# Relay_Sheet.net
KiCad netlist of a schematic drawn in Altium Designer
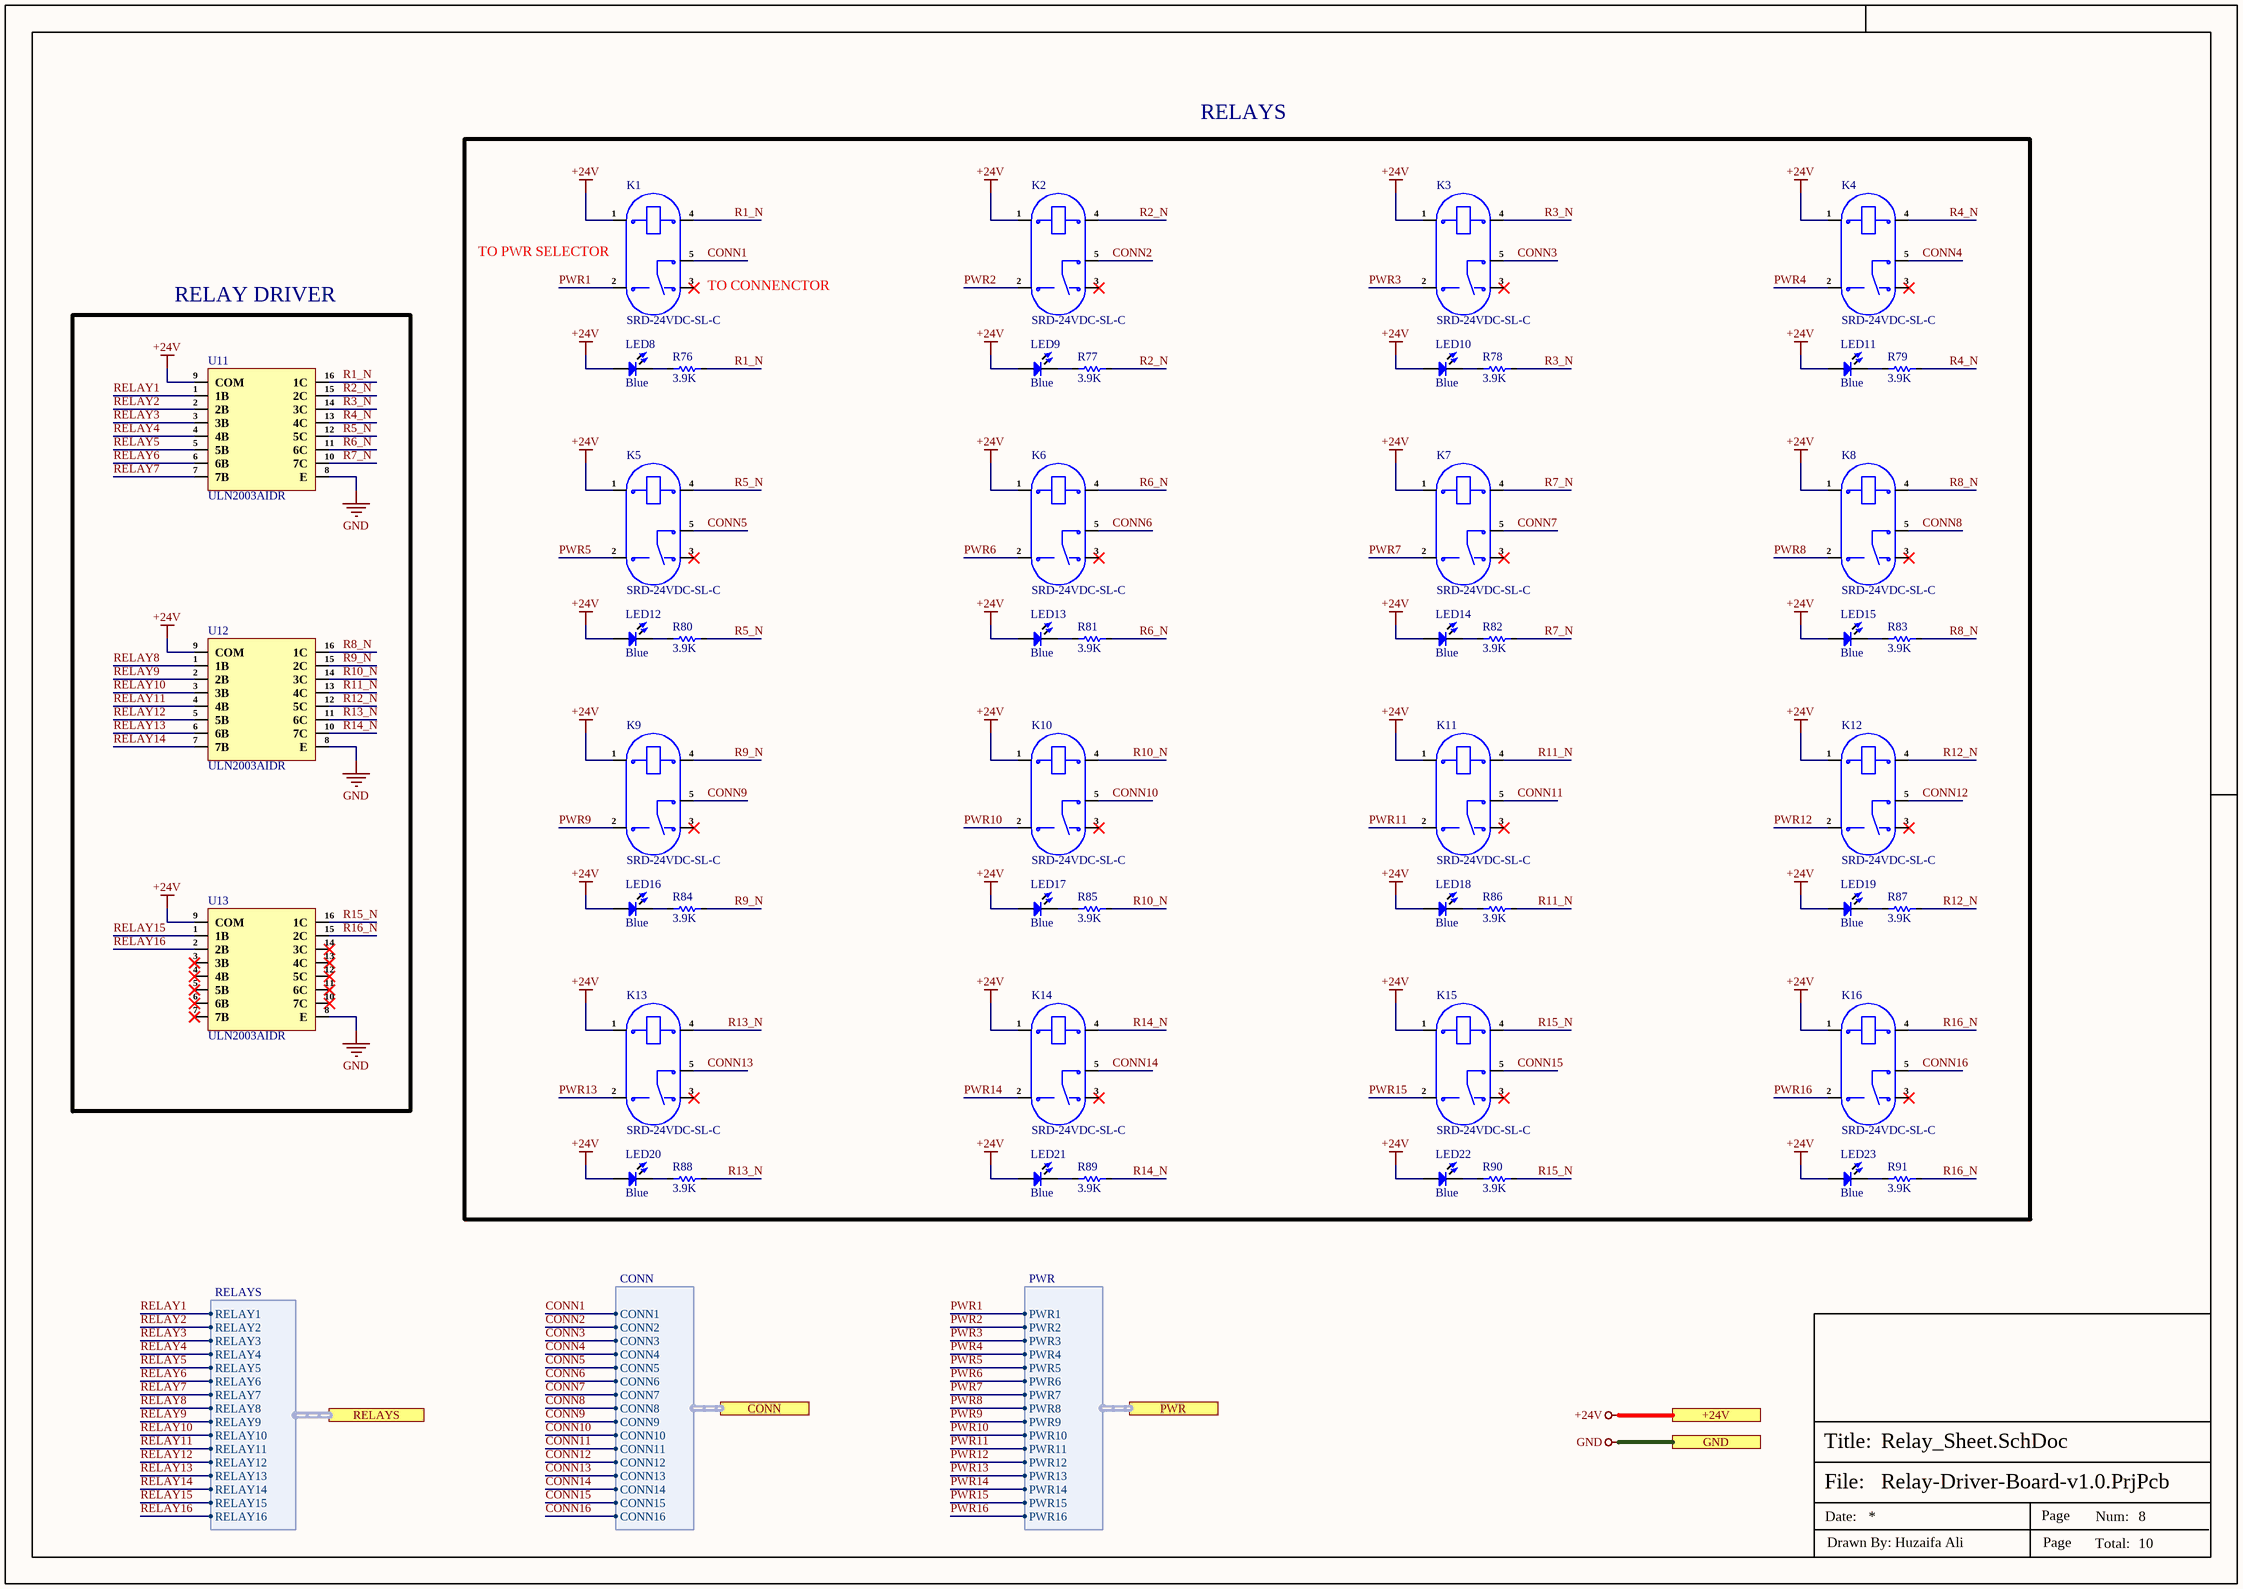
[diagram p0: Relay_Sheet.SchDoc]

(export (version "E")
  (design (tool "Eeschema 10.0.6"))
  (components
    (comp (ref "K1")
      (value "SRD-24VDC-SL-C")
      (footprint "SRD-24VDC-SL-C")
      (description "250V@AC 24V 15A SPDT (1 Form C) Plugin,15.6x19.2mm Power Relays ROHS")
      (fields (field (name "LCSC PART NUMBER") "C15840") (field (name "MANUFACTURER") "Ningbo Forward Relay"))
      (libsource (lib "eSpark Libraries") (part "SRD-24VDC-SL-C"))
    )
    (comp (ref "K2")
      (value "SRD-24VDC-SL-C")
      (footprint "SRD-24VDC-SL-C")
      (description "250V@AC 24V 15A SPDT (1 Form C) Plugin,15.6x19.2mm Power Relays ROHS")
      (fields (field (name "LCSC PART NUMBER") "C15840") (field (name "MANUFACTURER") "Ningbo Forward Relay"))
      (libsource (lib "eSpark Libraries") (part "SRD-24VDC-SL-C"))
    )
    (comp (ref "K3")
      (value "SRD-24VDC-SL-C")
      (footprint "SRD-24VDC-SL-C")
      (description "250V@AC 24V 15A SPDT (1 Form C) Plugin,15.6x19.2mm Power Relays ROHS")
      (fields (field (name "LCSC PART NUMBER") "C15840") (field (name "MANUFACTURER") "Ningbo Forward Relay"))
      (libsource (lib "eSpark Libraries") (part "SRD-24VDC-SL-C"))
    )
    (comp (ref "K4")
      (value "SRD-24VDC-SL-C")
      (footprint "SRD-24VDC-SL-C")
      (description "250V@AC 24V 15A SPDT (1 Form C) Plugin,15.6x19.2mm Power Relays ROHS")
      (fields (field (name "LCSC PART NUMBER") "C15840") (field (name "MANUFACTURER") "Ningbo Forward Relay"))
      (libsource (lib "eSpark Libraries") (part "SRD-24VDC-SL-C"))
    )
    (comp (ref "K5")
      (value "SRD-24VDC-SL-C")
      (footprint "SRD-24VDC-SL-C")
      (description "250V@AC 24V 15A SPDT (1 Form C) Plugin,15.6x19.2mm Power Relays ROHS")
      (fields (field (name "LCSC PART NUMBER") "C15840") (field (name "MANUFACTURER") "Ningbo Forward Relay"))
      (libsource (lib "eSpark Libraries") (part "SRD-24VDC-SL-C"))
    )
    (comp (ref "K6")
      (value "SRD-24VDC-SL-C")
      (footprint "SRD-24VDC-SL-C")
      (description "250V@AC 24V 15A SPDT (1 Form C) Plugin,15.6x19.2mm Power Relays ROHS")
      (fields (field (name "LCSC PART NUMBER") "C15840") (field (name "MANUFACTURER") "Ningbo Forward Relay"))
      (libsource (lib "eSpark Libraries") (part "SRD-24VDC-SL-C"))
    )
    (comp (ref "K7")
      (value "SRD-24VDC-SL-C")
      (footprint "SRD-24VDC-SL-C")
      (description "250V@AC 24V 15A SPDT (1 Form C) Plugin,15.6x19.2mm Power Relays ROHS")
      (fields (field (name "LCSC PART NUMBER") "C15840") (field (name "MANUFACTURER") "Ningbo Forward Relay"))
      (libsource (lib "eSpark Libraries") (part "SRD-24VDC-SL-C"))
    )
    (comp (ref "K8")
      (value "SRD-24VDC-SL-C")
      (footprint "SRD-24VDC-SL-C")
      (description "250V@AC 24V 15A SPDT (1 Form C) Plugin,15.6x19.2mm Power Relays ROHS")
      (fields (field (name "LCSC PART NUMBER") "C15840") (field (name "MANUFACTURER") "Ningbo Forward Relay"))
      (libsource (lib "eSpark Libraries") (part "SRD-24VDC-SL-C"))
    )
    (comp (ref "K9")
      (value "SRD-24VDC-SL-C")
      (footprint "SRD-24VDC-SL-C")
      (description "250V@AC 24V 15A SPDT (1 Form C) Plugin,15.6x19.2mm Power Relays ROHS")
      (fields (field (name "LCSC PART NUMBER") "C15840") (field (name "MANUFACTURER") "Ningbo Forward Relay"))
      (libsource (lib "eSpark Libraries") (part "SRD-24VDC-SL-C"))
    )
    (comp (ref "K10")
      (value "SRD-24VDC-SL-C")
      (footprint "SRD-24VDC-SL-C")
      (description "250V@AC 24V 15A SPDT (1 Form C) Plugin,15.6x19.2mm Power Relays ROHS")
      (fields (field (name "LCSC PART NUMBER") "C15840") (field (name "MANUFACTURER") "Ningbo Forward Relay"))
      (libsource (lib "eSpark Libraries") (part "SRD-24VDC-SL-C"))
    )
    (comp (ref "K11")
      (value "SRD-24VDC-SL-C")
      (footprint "SRD-24VDC-SL-C")
      (description "250V@AC 24V 15A SPDT (1 Form C) Plugin,15.6x19.2mm Power Relays ROHS")
      (fields (field (name "LCSC PART NUMBER") "C15840") (field (name "MANUFACTURER") "Ningbo Forward Relay"))
      (libsource (lib "eSpark Libraries") (part "SRD-24VDC-SL-C"))
    )
    (comp (ref "K12")
      (value "SRD-24VDC-SL-C")
      (footprint "SRD-24VDC-SL-C")
      (description "250V@AC 24V 15A SPDT (1 Form C) Plugin,15.6x19.2mm Power Relays ROHS")
      (fields (field (name "LCSC PART NUMBER") "C15840") (field (name "MANUFACTURER") "Ningbo Forward Relay"))
      (libsource (lib "eSpark Libraries") (part "SRD-24VDC-SL-C"))
    )
    (comp (ref "K13")
      (value "SRD-24VDC-SL-C")
      (footprint "SRD-24VDC-SL-C")
      (description "250V@AC 24V 15A SPDT (1 Form C) Plugin,15.6x19.2mm Power Relays ROHS")
      (fields (field (name "LCSC PART NUMBER") "C15840") (field (name "MANUFACTURER") "Ningbo Forward Relay"))
      (libsource (lib "eSpark Libraries") (part "SRD-24VDC-SL-C"))
    )
    (comp (ref "K14")
      (value "SRD-24VDC-SL-C")
      (footprint "SRD-24VDC-SL-C")
      (description "250V@AC 24V 15A SPDT (1 Form C) Plugin,15.6x19.2mm Power Relays ROHS")
      (fields (field (name "LCSC PART NUMBER") "C15840") (field (name "MANUFACTURER") "Ningbo Forward Relay"))
      (libsource (lib "eSpark Libraries") (part "SRD-24VDC-SL-C"))
    )
    (comp (ref "K15")
      (value "SRD-24VDC-SL-C")
      (footprint "SRD-24VDC-SL-C")
      (description "250V@AC 24V 15A SPDT (1 Form C) Plugin,15.6x19.2mm Power Relays ROHS")
      (fields (field (name "LCSC PART NUMBER") "C15840") (field (name "MANUFACTURER") "Ningbo Forward Relay"))
      (libsource (lib "eSpark Libraries") (part "SRD-24VDC-SL-C"))
    )
    (comp (ref "K16")
      (value "SRD-24VDC-SL-C")
      (footprint "SRD-24VDC-SL-C")
      (description "250V@AC 24V 15A SPDT (1 Form C) Plugin,15.6x19.2mm Power Relays ROHS")
      (fields (field (name "LCSC PART NUMBER") "C15840") (field (name "MANUFACTURER") "Ningbo Forward Relay"))
      (libsource (lib "eSpark Libraries") (part "SRD-24VDC-SL-C"))
    )
    (comp (ref "LED8")
      (value "Blue")
      (footprint "LED-0603")
      (description "blue 0603 Light Emitting Diodes (LED) ROHS")
      (fields
        (field (name "MANUFACTURER") "Foshan NationStar Optoelectronics")
        (field (name "MANUFACTURER PART NUMBER") "NCD0603B3")
      )
      (libsource (lib "eSpark Libraries") (part "NCD0603B3"))
    )
    (comp (ref "LED9")
      (value "Blue")
      (footprint "LED-0603")
      (description "blue 0603 Light Emitting Diodes (LED) ROHS")
      (fields
        (field (name "MANUFACTURER") "Foshan NationStar Optoelectronics")
        (field (name "MANUFACTURER PART NUMBER") "NCD0603B3")
      )
      (libsource (lib "eSpark Libraries") (part "NCD0603B3"))
    )
    (comp (ref "LED10")
      (value "Blue")
      (footprint "LED-0603")
      (description "blue 0603 Light Emitting Diodes (LED) ROHS")
      (fields
        (field (name "MANUFACTURER") "Foshan NationStar Optoelectronics")
        (field (name "MANUFACTURER PART NUMBER") "NCD0603B3")
      )
      (libsource (lib "eSpark Libraries") (part "NCD0603B3"))
    )
    (comp (ref "LED11")
      (value "Blue")
      (footprint "LED-0603")
      (description "blue 0603 Light Emitting Diodes (LED) ROHS")
      (fields
        (field (name "MANUFACTURER") "Foshan NationStar Optoelectronics")
        (field (name "MANUFACTURER PART NUMBER") "NCD0603B3")
      )
      (libsource (lib "eSpark Libraries") (part "NCD0603B3"))
    )
    (comp (ref "LED12")
      (value "Blue")
      (footprint "LED-0603")
      (description "blue 0603 Light Emitting Diodes (LED) ROHS")
      (fields
        (field (name "MANUFACTURER") "Foshan NationStar Optoelectronics")
        (field (name "MANUFACTURER PART NUMBER") "NCD0603B3")
      )
      (libsource (lib "eSpark Libraries") (part "NCD0603B3"))
    )
    (comp (ref "LED13")
      (value "Blue")
      (footprint "LED-0603")
      (description "blue 0603 Light Emitting Diodes (LED) ROHS")
      (fields
        (field (name "MANUFACTURER") "Foshan NationStar Optoelectronics")
        (field (name "MANUFACTURER PART NUMBER") "NCD0603B3")
      )
      (libsource (lib "eSpark Libraries") (part "NCD0603B3"))
    )
    (comp (ref "LED14")
      (value "Blue")
      (footprint "LED-0603")
      (description "blue 0603 Light Emitting Diodes (LED) ROHS")
      (fields
        (field (name "MANUFACTURER") "Foshan NationStar Optoelectronics")
        (field (name "MANUFACTURER PART NUMBER") "NCD0603B3")
      )
      (libsource (lib "eSpark Libraries") (part "NCD0603B3"))
    )
    (comp (ref "LED15")
      (value "Blue")
      (footprint "LED-0603")
      (description "blue 0603 Light Emitting Diodes (LED) ROHS")
      (fields
        (field (name "MANUFACTURER") "Foshan NationStar Optoelectronics")
        (field (name "MANUFACTURER PART NUMBER") "NCD0603B3")
      )
      (libsource (lib "eSpark Libraries") (part "NCD0603B3"))
    )
    (comp (ref "LED16")
      (value "Blue")
      (footprint "LED-0603")
      (description "blue 0603 Light Emitting Diodes (LED) ROHS")
      (fields
        (field (name "MANUFACTURER") "Foshan NationStar Optoelectronics")
        (field (name "MANUFACTURER PART NUMBER") "NCD0603B3")
      )
      (libsource (lib "eSpark Libraries") (part "NCD0603B3"))
    )
    (comp (ref "LED17")
      (value "Blue")
      (footprint "LED-0603")
      (description "blue 0603 Light Emitting Diodes (LED) ROHS")
      (fields
        (field (name "MANUFACTURER") "Foshan NationStar Optoelectronics")
        (field (name "MANUFACTURER PART NUMBER") "NCD0603B3")
      )
      (libsource (lib "eSpark Libraries") (part "NCD0603B3"))
    )
    (comp (ref "LED18")
      (value "Blue")
      (footprint "LED-0603")
      (description "blue 0603 Light Emitting Diodes (LED) ROHS")
      (fields
        (field (name "MANUFACTURER") "Foshan NationStar Optoelectronics")
        (field (name "MANUFACTURER PART NUMBER") "NCD0603B3")
      )
      (libsource (lib "eSpark Libraries") (part "NCD0603B3"))
    )
    (comp (ref "LED19")
      (value "Blue")
      (footprint "LED-0603")
      (description "blue 0603 Light Emitting Diodes (LED) ROHS")
      (fields
        (field (name "MANUFACTURER") "Foshan NationStar Optoelectronics")
        (field (name "MANUFACTURER PART NUMBER") "NCD0603B3")
      )
      (libsource (lib "eSpark Libraries") (part "NCD0603B3"))
    )
    (comp (ref "LED20")
      (value "Blue")
      (footprint "LED-0603")
      (description "blue 0603 Light Emitting Diodes (LED) ROHS")
      (fields
        (field (name "MANUFACTURER") "Foshan NationStar Optoelectronics")
        (field (name "MANUFACTURER PART NUMBER") "NCD0603B3")
      )
      (libsource (lib "eSpark Libraries") (part "NCD0603B3"))
    )
    (comp (ref "LED21")
      (value "Blue")
      (footprint "LED-0603")
      (description "blue 0603 Light Emitting Diodes (LED) ROHS")
      (fields
        (field (name "MANUFACTURER") "Foshan NationStar Optoelectronics")
        (field (name "MANUFACTURER PART NUMBER") "NCD0603B3")
      )
      (libsource (lib "eSpark Libraries") (part "NCD0603B3"))
    )
    (comp (ref "LED22")
      (value "Blue")
      (footprint "LED-0603")
      (description "blue 0603 Light Emitting Diodes (LED) ROHS")
      (fields
        (field (name "MANUFACTURER") "Foshan NationStar Optoelectronics")
        (field (name "MANUFACTURER PART NUMBER") "NCD0603B3")
      )
      (libsource (lib "eSpark Libraries") (part "NCD0603B3"))
    )
    (comp (ref "LED23")
      (value "Blue")
      (footprint "LED-0603")
      (description "blue 0603 Light Emitting Diodes (LED) ROHS")
      (fields
        (field (name "MANUFACTURER") "Foshan NationStar Optoelectronics")
        (field (name "MANUFACTURER PART NUMBER") "NCD0603B3")
      )
      (libsource (lib "eSpark Libraries") (part "NCD0603B3"))
    )
    (comp (ref "R76")
      (value "3.9K")
      (footprint "Res-0402")
      (description "RES 3.9K OHM 1% 1/16W 0402")
      (fields
        (field (name "MANUFACTURER") "Yageo")
        (field (name "MANUFACTURER PART NUMBER") "RC0402FR-073K9L")
      )
      (libsource (lib "eSpark Libraries") (part "RC0402FR-073K9L"))
    )
    (comp (ref "R77")
      (value "3.9K")
      (footprint "Res-0402")
      (description "RES 3.9K OHM 1% 1/16W 0402")
      (fields
        (field (name "MANUFACTURER") "Yageo")
        (field (name "MANUFACTURER PART NUMBER") "RC0402FR-073K9L")
      )
      (libsource (lib "eSpark Libraries") (part "RC0402FR-073K9L"))
    )
    (comp (ref "R78")
      (value "3.9K")
      (footprint "Res-0402")
      (description "RES 3.9K OHM 1% 1/16W 0402")
      (fields
        (field (name "MANUFACTURER") "Yageo")
        (field (name "MANUFACTURER PART NUMBER") "RC0402FR-073K9L")
      )
      (libsource (lib "eSpark Libraries") (part "RC0402FR-073K9L"))
    )
    (comp (ref "R79")
      (value "3.9K")
      (footprint "Res-0402")
      (description "RES 3.9K OHM 1% 1/16W 0402")
      (fields
        (field (name "MANUFACTURER") "Yageo")
        (field (name "MANUFACTURER PART NUMBER") "RC0402FR-073K9L")
      )
      (libsource (lib "eSpark Libraries") (part "RC0402FR-073K9L"))
    )
    (comp (ref "R80")
      (value "3.9K")
      (footprint "Res-0402")
      (description "RES 3.9K OHM 1% 1/16W 0402")
      (fields
        (field (name "MANUFACTURER") "Yageo")
        (field (name "MANUFACTURER PART NUMBER") "RC0402FR-073K9L")
      )
      (libsource (lib "eSpark Libraries") (part "RC0402FR-073K9L"))
    )
    (comp (ref "R81")
      (value "3.9K")
      (footprint "Res-0402")
      (description "RES 3.9K OHM 1% 1/16W 0402")
      (fields
        (field (name "MANUFACTURER") "Yageo")
        (field (name "MANUFACTURER PART NUMBER") "RC0402FR-073K9L")
      )
      (libsource (lib "eSpark Libraries") (part "RC0402FR-073K9L"))
    )
    (comp (ref "R82")
      (value "3.9K")
      (footprint "Res-0402")
      (description "RES 3.9K OHM 1% 1/16W 0402")
      (fields
        (field (name "MANUFACTURER") "Yageo")
        (field (name "MANUFACTURER PART NUMBER") "RC0402FR-073K9L")
      )
      (libsource (lib "eSpark Libraries") (part "RC0402FR-073K9L"))
    )
    (comp (ref "R83")
      (value "3.9K")
      (footprint "Res-0402")
      (description "RES 3.9K OHM 1% 1/16W 0402")
      (fields
        (field (name "MANUFACTURER") "Yageo")
        (field (name "MANUFACTURER PART NUMBER") "RC0402FR-073K9L")
      )
      (libsource (lib "eSpark Libraries") (part "RC0402FR-073K9L"))
    )
    (comp (ref "R84")
      (value "3.9K")
      (footprint "Res-0402")
      (description "RES 3.9K OHM 1% 1/16W 0402")
      (fields
        (field (name "MANUFACTURER") "Yageo")
        (field (name "MANUFACTURER PART NUMBER") "RC0402FR-073K9L")
      )
      (libsource (lib "eSpark Libraries") (part "RC0402FR-073K9L"))
    )
    (comp (ref "R85")
      (value "3.9K")
      (footprint "Res-0402")
      (description "RES 3.9K OHM 1% 1/16W 0402")
      (fields
        (field (name "MANUFACTURER") "Yageo")
        (field (name "MANUFACTURER PART NUMBER") "RC0402FR-073K9L")
      )
      (libsource (lib "eSpark Libraries") (part "RC0402FR-073K9L"))
    )
    (comp (ref "R86")
      (value "3.9K")
      (footprint "Res-0402")
      (description "RES 3.9K OHM 1% 1/16W 0402")
      (fields
        (field (name "MANUFACTURER") "Yageo")
        (field (name "MANUFACTURER PART NUMBER") "RC0402FR-073K9L")
      )
      (libsource (lib "eSpark Libraries") (part "RC0402FR-073K9L"))
    )
    (comp (ref "R87")
      (value "3.9K")
      (footprint "Res-0402")
      (description "RES 3.9K OHM 1% 1/16W 0402")
      (fields
        (field (name "MANUFACTURER") "Yageo")
        (field (name "MANUFACTURER PART NUMBER") "RC0402FR-073K9L")
      )
      (libsource (lib "eSpark Libraries") (part "RC0402FR-073K9L"))
    )
    (comp (ref "R88")
      (value "3.9K")
      (footprint "Res-0402")
      (description "RES 3.9K OHM 1% 1/16W 0402")
      (fields
        (field (name "MANUFACTURER") "Yageo")
        (field (name "MANUFACTURER PART NUMBER") "RC0402FR-073K9L")
      )
      (libsource (lib "eSpark Libraries") (part "RC0402FR-073K9L"))
    )
    (comp (ref "R89")
      (value "3.9K")
      (footprint "Res-0402")
      (description "RES 3.9K OHM 1% 1/16W 0402")
      (fields
        (field (name "MANUFACTURER") "Yageo")
        (field (name "MANUFACTURER PART NUMBER") "RC0402FR-073K9L")
      )
      (libsource (lib "eSpark Libraries") (part "RC0402FR-073K9L"))
    )
    (comp (ref "R90")
      (value "3.9K")
      (footprint "Res-0402")
      (description "RES 3.9K OHM 1% 1/16W 0402")
      (fields
        (field (name "MANUFACTURER") "Yageo")
        (field (name "MANUFACTURER PART NUMBER") "RC0402FR-073K9L")
      )
      (libsource (lib "eSpark Libraries") (part "RC0402FR-073K9L"))
    )
    (comp (ref "R91")
      (value "3.9K")
      (footprint "Res-0402")
      (description "RES 3.9K OHM 1% 1/16W 0402")
      (fields
        (field (name "MANUFACTURER") "Yageo")
        (field (name "MANUFACTURER PART NUMBER") "RC0402FR-073K9L")
      )
      (libsource (lib "eSpark Libraries") (part "RC0402FR-073K9L"))
    )
    (comp (ref "U11")
      (value "ULN2003AIDR")
      (footprint "16-SOIC (0.154\", 3.90mm Width)")
      (description "IC PWR RELAY 7NPN 1:1 16SOIC")
      (fields (field (name "MANUFACTURER") "Texas Instruments"))
      (libsource (lib "eSpark Libraries") (part "ULN2003AIDR"))
    )
    (comp (ref "U12")
      (value "ULN2003AIDR")
      (footprint "16-SOIC (0.154\", 3.90mm Width)")
      (description "IC PWR RELAY 7NPN 1:1 16SOIC")
      (fields (field (name "MANUFACTURER") "Texas Instruments"))
      (libsource (lib "eSpark Libraries") (part "ULN2003AIDR"))
    )
    (comp (ref "U13")
      (value "ULN2003AIDR")
      (footprint "16-SOIC (0.154\", 3.90mm Width)")
      (description "IC PWR RELAY 7NPN 1:1 16SOIC")
      (fields (field (name "MANUFACTURER") "Texas Instruments"))
      (libsource (lib "eSpark Libraries") (part "ULN2003AIDR"))
    )
  )
  (nets
    (net (code "4") (name "+24V") (class "Default")
      (node (ref "K1") (pin "1") (pinfunction "1_1") (pintype "passive"))
      (node (ref "K10") (pin "1") (pinfunction "1_1") (pintype "passive"))
      (node (ref "K11") (pin "1") (pinfunction "1_1") (pintype "passive"))
      (node (ref "K12") (pin "1") (pinfunction "1_1") (pintype "passive"))
      (node (ref "K13") (pin "1") (pinfunction "1_1") (pintype "passive"))
      (node (ref "K14") (pin "1") (pinfunction "1_1") (pintype "passive"))
      (node (ref "K15") (pin "1") (pinfunction "1_1") (pintype "passive"))
      (node (ref "K16") (pin "1") (pinfunction "1_1") (pintype "passive"))
      (node (ref "K2") (pin "1") (pinfunction "1_1") (pintype "passive"))
      (node (ref "K3") (pin "1") (pinfunction "1_1") (pintype "passive"))
      (node (ref "K4") (pin "1") (pinfunction "1_1") (pintype "passive"))
      (node (ref "K5") (pin "1") (pinfunction "1_1") (pintype "passive"))
      (node (ref "K6") (pin "1") (pinfunction "1_1") (pintype "passive"))
      (node (ref "K7") (pin "1") (pinfunction "1_1") (pintype "passive"))
      (node (ref "K8") (pin "1") (pinfunction "1_1") (pintype "passive"))
      (node (ref "K9") (pin "1") (pinfunction "1_1") (pintype "passive"))
      (node (ref "LED10") (pin "1") (pinfunction "1_1") (pintype "passive"))
      (node (ref "LED11") (pin "1") (pinfunction "1_1") (pintype "passive"))
      (node (ref "LED12") (pin "1") (pinfunction "1_1") (pintype "passive"))
      (node (ref "LED13") (pin "1") (pinfunction "1_1") (pintype "passive"))
      (node (ref "LED14") (pin "1") (pinfunction "1_1") (pintype "passive"))
      (node (ref "LED15") (pin "1") (pinfunction "1_1") (pintype "passive"))
      (node (ref "LED16") (pin "1") (pinfunction "1_1") (pintype "passive"))
      (node (ref "LED17") (pin "1") (pinfunction "1_1") (pintype "passive"))
      (node (ref "LED18") (pin "1") (pinfunction "1_1") (pintype "passive"))
      (node (ref "LED19") (pin "1") (pinfunction "1_1") (pintype "passive"))
      (node (ref "LED20") (pin "1") (pinfunction "1_1") (pintype "passive"))
      (node (ref "LED21") (pin "1") (pinfunction "1_1") (pintype "passive"))
      (node (ref "LED22") (pin "1") (pinfunction "1_1") (pintype "passive"))
      (node (ref "LED23") (pin "1") (pinfunction "1_1") (pintype "passive"))
      (node (ref "LED8") (pin "1") (pinfunction "1_1") (pintype "passive"))
      (node (ref "LED9") (pin "1") (pinfunction "1_1") (pintype "passive"))
      (node (ref "U11") (pin "9") (pinfunction "COM_9") (pintype "passive"))
      (node (ref "U12") (pin "9") (pinfunction "COM_9") (pintype "passive"))
      (node (ref "U13") (pin "9") (pinfunction "COM_9") (pintype "passive"))
    )
    (net (code "5") (name "/CONN1") (class "Default")
      (node (ref "K1") (pin "5") (pinfunction "5_5") (pintype "passive"))
    )
    (net (code "6") (name "/CONN2") (class "Default")
      (node (ref "K2") (pin "5") (pinfunction "5_5") (pintype "passive"))
    )
    (net (code "7") (name "/CONN3") (class "Default")
      (node (ref "K3") (pin "5") (pinfunction "5_5") (pintype "passive"))
    )
    (net (code "8") (name "/CONN4") (class "Default")
      (node (ref "K4") (pin "5") (pinfunction "5_5") (pintype "passive"))
    )
    (net (code "9") (name "/CONN5") (class "Default")
      (node (ref "K5") (pin "5") (pinfunction "5_5") (pintype "passive"))
    )
    (net (code "10") (name "/CONN6") (class "Default")
      (node (ref "K6") (pin "5") (pinfunction "5_5") (pintype "passive"))
    )
    (net (code "11") (name "/CONN7") (class "Default")
      (node (ref "K7") (pin "5") (pinfunction "5_5") (pintype "passive"))
    )
    (net (code "12") (name "/CONN8") (class "Default")
      (node (ref "K8") (pin "5") (pinfunction "5_5") (pintype "passive"))
    )
    (net (code "13") (name "/CONN9") (class "Default")
      (node (ref "K9") (pin "5") (pinfunction "5_5") (pintype "passive"))
    )
    (net (code "14") (name "/CONN10") (class "Default")
      (node (ref "K10") (pin "5") (pinfunction "5_5") (pintype "passive"))
    )
    (net (code "15") (name "/CONN11") (class "Default")
      (node (ref "K11") (pin "5") (pinfunction "5_5") (pintype "passive"))
    )
    (net (code "16") (name "/CONN12") (class "Default")
      (node (ref "K12") (pin "5") (pinfunction "5_5") (pintype "passive"))
    )
    (net (code "17") (name "/CONN13") (class "Default")
      (node (ref "K13") (pin "5") (pinfunction "5_5") (pintype "passive"))
    )
    (net (code "18") (name "/CONN14") (class "Default")
      (node (ref "K14") (pin "5") (pinfunction "5_5") (pintype "passive"))
    )
    (net (code "19") (name "/CONN15") (class "Default")
      (node (ref "K15") (pin "5") (pinfunction "5_5") (pintype "passive"))
    )
    (net (code "20") (name "/CONN16") (class "Default")
      (node (ref "K16") (pin "5") (pinfunction "5_5") (pintype "passive"))
    )
    (net (code "21") (name "/PWR1") (class "Default")
      (node (ref "K1") (pin "2") (pinfunction "2_2") (pintype "passive"))
    )
    (net (code "22") (name "/PWR2") (class "Default")
      (node (ref "K2") (pin "2") (pinfunction "2_2") (pintype "passive"))
    )
    (net (code "23") (name "/PWR3") (class "Default")
      (node (ref "K3") (pin "2") (pinfunction "2_2") (pintype "passive"))
    )
    (net (code "24") (name "/PWR4") (class "Default")
      (node (ref "K4") (pin "2") (pinfunction "2_2") (pintype "passive"))
    )
    (net (code "25") (name "/PWR5") (class "Default")
      (node (ref "K5") (pin "2") (pinfunction "2_2") (pintype "passive"))
    )
    (net (code "26") (name "/PWR6") (class "Default")
      (node (ref "K6") (pin "2") (pinfunction "2_2") (pintype "passive"))
    )
    (net (code "27") (name "/PWR7") (class "Default")
      (node (ref "K7") (pin "2") (pinfunction "2_2") (pintype "passive"))
    )
    (net (code "28") (name "/PWR8") (class "Default")
      (node (ref "K8") (pin "2") (pinfunction "2_2") (pintype "passive"))
    )
    (net (code "29") (name "/PWR9") (class "Default")
      (node (ref "K9") (pin "2") (pinfunction "2_2") (pintype "passive"))
    )
    (net (code "30") (name "/PWR10") (class "Default")
      (node (ref "K10") (pin "2") (pinfunction "2_2") (pintype "passive"))
    )
    (net (code "31") (name "/PWR11") (class "Default")
      (node (ref "K11") (pin "2") (pinfunction "2_2") (pintype "passive"))
    )
    (net (code "32") (name "/PWR12") (class "Default")
      (node (ref "K12") (pin "2") (pinfunction "2_2") (pintype "passive"))
    )
    (net (code "33") (name "/PWR13") (class "Default")
      (node (ref "K13") (pin "2") (pinfunction "2_2") (pintype "passive"))
    )
    (net (code "34") (name "/PWR14") (class "Default")
      (node (ref "K14") (pin "2") (pinfunction "2_2") (pintype "passive"))
    )
    (net (code "35") (name "/PWR15") (class "Default")
      (node (ref "K15") (pin "2") (pinfunction "2_2") (pintype "passive"))
    )
    (net (code "36") (name "/PWR16") (class "Default")
      (node (ref "K16") (pin "2") (pinfunction "2_2") (pintype "passive"))
    )
    (net (code "37") (name "/R1_N") (class "Default")
      (node (ref "K1") (pin "4") (pinfunction "4_4") (pintype "passive"))
      (node (ref "R76") (pin "2") (pinfunction "2_2") (pintype "passive"))
      (node (ref "U11") (pin "16") (pinfunction "1C_16") (pintype "passive"))
    )
    (net (code "38") (name "/R2_N") (class "Default")
      (node (ref "K2") (pin "4") (pinfunction "4_4") (pintype "passive"))
      (node (ref "R77") (pin "2") (pinfunction "2_2") (pintype "passive"))
      (node (ref "U11") (pin "15") (pinfunction "2C_15") (pintype "passive"))
    )
    (net (code "39") (name "/R3_N") (class "Default")
      (node (ref "K3") (pin "4") (pinfunction "4_4") (pintype "passive"))
      (node (ref "R78") (pin "2") (pinfunction "2_2") (pintype "passive"))
      (node (ref "U11") (pin "14") (pinfunction "3C_14") (pintype "passive"))
    )
    (net (code "40") (name "/R4_N") (class "Default")
      (node (ref "K4") (pin "4") (pinfunction "4_4") (pintype "passive"))
      (node (ref "R79") (pin "2") (pinfunction "2_2") (pintype "passive"))
      (node (ref "U11") (pin "13") (pinfunction "4C_13") (pintype "passive"))
    )
    (net (code "41") (name "/R5_N") (class "Default")
      (node (ref "K5") (pin "4") (pinfunction "4_4") (pintype "passive"))
      (node (ref "R80") (pin "2") (pinfunction "2_2") (pintype "passive"))
      (node (ref "U11") (pin "12") (pinfunction "5C_12") (pintype "passive"))
    )
    (net (code "42") (name "/R6_N") (class "Default")
      (node (ref "K6") (pin "4") (pinfunction "4_4") (pintype "passive"))
      (node (ref "R81") (pin "2") (pinfunction "2_2") (pintype "passive"))
      (node (ref "U11") (pin "11") (pinfunction "6C_11") (pintype "passive"))
    )
    (net (code "43") (name "/R7_N") (class "Default")
      (node (ref "K7") (pin "4") (pinfunction "4_4") (pintype "passive"))
      (node (ref "R82") (pin "2") (pinfunction "2_2") (pintype "passive"))
      (node (ref "U11") (pin "10") (pinfunction "7C_10") (pintype "passive"))
    )
    (net (code "44") (name "/R8_N") (class "Default")
      (node (ref "K8") (pin "4") (pinfunction "4_4") (pintype "passive"))
      (node (ref "R83") (pin "2") (pinfunction "2_2") (pintype "passive"))
      (node (ref "U12") (pin "16") (pinfunction "1C_16") (pintype "passive"))
    )
    (net (code "45") (name "/R9_N") (class "Default")
      (node (ref "K9") (pin "4") (pinfunction "4_4") (pintype "passive"))
      (node (ref "R84") (pin "2") (pinfunction "2_2") (pintype "passive"))
      (node (ref "U12") (pin "15") (pinfunction "2C_15") (pintype "passive"))
    )
    (net (code "46") (name "/R10_N") (class "Default")
      (node (ref "K10") (pin "4") (pinfunction "4_4") (pintype "passive"))
      (node (ref "R85") (pin "2") (pinfunction "2_2") (pintype "passive"))
      (node (ref "U12") (pin "14") (pinfunction "3C_14") (pintype "passive"))
    )
    (net (code "47") (name "/R11_N") (class "Default")
      (node (ref "K11") (pin "4") (pinfunction "4_4") (pintype "passive"))
      (node (ref "R86") (pin "2") (pinfunction "2_2") (pintype "passive"))
      (node (ref "U12") (pin "13") (pinfunction "4C_13") (pintype "passive"))
    )
    (net (code "48") (name "/R12_N") (class "Default")
      (node (ref "K12") (pin "4") (pinfunction "4_4") (pintype "passive"))
      (node (ref "R87") (pin "2") (pinfunction "2_2") (pintype "passive"))
      (node (ref "U12") (pin "12") (pinfunction "5C_12") (pintype "passive"))
    )
    (net (code "49") (name "/R13_N") (class "Default")
      (node (ref "K13") (pin "4") (pinfunction "4_4") (pintype "passive"))
      (node (ref "R88") (pin "2") (pinfunction "2_2") (pintype "passive"))
      (node (ref "U12") (pin "11") (pinfunction "6C_11") (pintype "passive"))
    )
    (net (code "50") (name "/R14_N") (class "Default")
      (node (ref "K14") (pin "4") (pinfunction "4_4") (pintype "passive"))
      (node (ref "R89") (pin "2") (pinfunction "2_2") (pintype "passive"))
      (node (ref "U12") (pin "10") (pinfunction "7C_10") (pintype "passive"))
    )
    (net (code "51") (name "/R15_N") (class "Default")
      (node (ref "K15") (pin "4") (pinfunction "4_4") (pintype "passive"))
      (node (ref "R90") (pin "2") (pinfunction "2_2") (pintype "passive"))
      (node (ref "U13") (pin "16") (pinfunction "1C_16") (pintype "passive"))
    )
    (net (code "52") (name "/R16_N") (class "Default")
      (node (ref "K16") (pin "4") (pinfunction "4_4") (pintype "passive"))
      (node (ref "R91") (pin "2") (pinfunction "2_2") (pintype "passive"))
      (node (ref "U13") (pin "15") (pinfunction "2C_15") (pintype "passive"))
    )
    (net (code "53") (name "/RELAY1") (class "Default")
      (node (ref "U11") (pin "1") (pinfunction "1B_1") (pintype "passive"))
    )
    (net (code "54") (name "/RELAY2") (class "Default")
      (node (ref "U11") (pin "2") (pinfunction "2B_2") (pintype "passive"))
    )
    (net (code "55") (name "/RELAY3") (class "Default")
      (node (ref "U11") (pin "3") (pinfunction "3B_3") (pintype "passive"))
    )
    (net (code "56") (name "/RELAY4") (class "Default")
      (node (ref "U11") (pin "4") (pinfunction "4B_4") (pintype "passive"))
    )
    (net (code "57") (name "/RELAY5") (class "Default")
      (node (ref "U11") (pin "5") (pinfunction "5B_5") (pintype "passive"))
    )
    (net (code "58") (name "/RELAY6") (class "Default")
      (node (ref "U11") (pin "6") (pinfunction "6B_6") (pintype "passive"))
    )
    (net (code "59") (name "/RELAY7") (class "Default")
      (node (ref "U11") (pin "7") (pinfunction "7B_7") (pintype "passive"))
    )
    (net (code "60") (name "/RELAY8") (class "Default")
      (node (ref "U12") (pin "1") (pinfunction "1B_1") (pintype "passive"))
    )
    (net (code "61") (name "/RELAY9") (class "Default")
      (node (ref "U12") (pin "2") (pinfunction "2B_2") (pintype "passive"))
    )
    (net (code "62") (name "/RELAY10") (class "Default")
      (node (ref "U12") (pin "3") (pinfunction "3B_3") (pintype "passive"))
    )
    (net (code "63") (name "/RELAY11") (class "Default")
      (node (ref "U12") (pin "4") (pinfunction "4B_4") (pintype "passive"))
    )
    (net (code "64") (name "/RELAY12") (class "Default")
      (node (ref "U12") (pin "5") (pinfunction "5B_5") (pintype "passive"))
    )
    (net (code "65") (name "/RELAY13") (class "Default")
      (node (ref "U12") (pin "6") (pinfunction "6B_6") (pintype "passive"))
    )
    (net (code "66") (name "/RELAY14") (class "Default")
      (node (ref "U12") (pin "7") (pinfunction "7B_7") (pintype "passive"))
    )
    (net (code "67") (name "/RELAY15") (class "Default")
      (node (ref "U13") (pin "1") (pinfunction "1B_1") (pintype "passive"))
    )
    (net (code "68") (name "/RELAY16") (class "Default")
      (node (ref "U13") (pin "2") (pinfunction "2B_2") (pintype "passive"))
    )
    (net (code "72") (name "GND") (class "Default")
      (node (ref "U11") (pin "8") (pinfunction "E_8") (pintype "passive"))
      (node (ref "U12") (pin "8") (pinfunction "E_8") (pintype "passive"))
      (node (ref "U13") (pin "8") (pinfunction "E_8") (pintype "passive"))
    )
    (net (code "73") (name "Net-(LED8-Pad2)") (class "Default")
      (node (ref "LED8") (pin "2") (pinfunction "2_2") (pintype "passive"))
      (node (ref "R76") (pin "1") (pinfunction "1_1") (pintype "passive"))
    )
    (net (code "74") (name "Net-(LED9-Pad2)") (class "Default")
      (node (ref "LED9") (pin "2") (pinfunction "2_2") (pintype "passive"))
      (node (ref "R77") (pin "1") (pinfunction "1_1") (pintype "passive"))
    )
    (net (code "75") (name "Net-(LED10-Pad2)") (class "Default")
      (node (ref "LED10") (pin "2") (pinfunction "2_2") (pintype "passive"))
      (node (ref "R78") (pin "1") (pinfunction "1_1") (pintype "passive"))
    )
    (net (code "76") (name "Net-(LED11-Pad2)") (class "Default")
      (node (ref "LED11") (pin "2") (pinfunction "2_2") (pintype "passive"))
      (node (ref "R79") (pin "1") (pinfunction "1_1") (pintype "passive"))
    )
    (net (code "77") (name "Net-(LED12-Pad2)") (class "Default")
      (node (ref "LED12") (pin "2") (pinfunction "2_2") (pintype "passive"))
      (node (ref "R80") (pin "1") (pinfunction "1_1") (pintype "passive"))
    )
    (net (code "78") (name "Net-(LED13-Pad2)") (class "Default")
      (node (ref "LED13") (pin "2") (pinfunction "2_2") (pintype "passive"))
      (node (ref "R81") (pin "1") (pinfunction "1_1") (pintype "passive"))
    )
    (net (code "79") (name "Net-(LED14-Pad2)") (class "Default")
      (node (ref "LED14") (pin "2") (pinfunction "2_2") (pintype "passive"))
      (node (ref "R82") (pin "1") (pinfunction "1_1") (pintype "passive"))
    )
    (net (code "80") (name "Net-(LED15-Pad2)") (class "Default")
      (node (ref "LED15") (pin "2") (pinfunction "2_2") (pintype "passive"))
      (node (ref "R83") (pin "1") (pinfunction "1_1") (pintype "passive"))
    )
    (net (code "81") (name "Net-(LED16-Pad2)") (class "Default")
      (node (ref "LED16") (pin "2") (pinfunction "2_2") (pintype "passive"))
      (node (ref "R84") (pin "1") (pinfunction "1_1") (pintype "passive"))
    )
    (net (code "82") (name "Net-(LED17-Pad2)") (class "Default")
      (node (ref "LED17") (pin "2") (pinfunction "2_2") (pintype "passive"))
      (node (ref "R85") (pin "1") (pinfunction "1_1") (pintype "passive"))
    )
    (net (code "83") (name "Net-(LED18-Pad2)") (class "Default")
      (node (ref "LED18") (pin "2") (pinfunction "2_2") (pintype "passive"))
      (node (ref "R86") (pin "1") (pinfunction "1_1") (pintype "passive"))
    )
    (net (code "84") (name "Net-(LED19-Pad2)") (class "Default")
      (node (ref "LED19") (pin "2") (pinfunction "2_2") (pintype "passive"))
      (node (ref "R87") (pin "1") (pinfunction "1_1") (pintype "passive"))
    )
    (net (code "85") (name "Net-(LED20-Pad2)") (class "Default")
      (node (ref "LED20") (pin "2") (pinfunction "2_2") (pintype "passive"))
      (node (ref "R88") (pin "1") (pinfunction "1_1") (pintype "passive"))
    )
    (net (code "86") (name "Net-(LED21-Pad2)") (class "Default")
      (node (ref "LED21") (pin "2") (pinfunction "2_2") (pintype "passive"))
      (node (ref "R89") (pin "1") (pinfunction "1_1") (pintype "passive"))
    )
    (net (code "87") (name "Net-(LED22-Pad2)") (class "Default")
      (node (ref "LED22") (pin "2") (pinfunction "2_2") (pintype "passive"))
      (node (ref "R90") (pin "1") (pinfunction "1_1") (pintype "passive"))
    )
    (net (code "88") (name "Net-(LED23-Pad2)") (class "Default")
      (node (ref "LED23") (pin "2") (pinfunction "2_2") (pintype "passive"))
      (node (ref "R91") (pin "1") (pinfunction "1_1") (pintype "passive"))
    )
    (net (code "89") (name "unconnected-(K1-Pad3)") (class "Default")
      (node (ref "K1") (pin "3") (pinfunction "3_3") (pintype "passive+no_connect"))
    )
    (net (code "90") (name "unconnected-(K2-Pad3)") (class "Default")
      (node (ref "K2") (pin "3") (pinfunction "3_3") (pintype "passive+no_connect"))
    )
    (net (code "91") (name "unconnected-(K3-Pad3)") (class "Default")
      (node (ref "K3") (pin "3") (pinfunction "3_3") (pintype "passive+no_connect"))
    )
    (net (code "92") (name "unconnected-(K4-Pad3)") (class "Default")
      (node (ref "K4") (pin "3") (pinfunction "3_3") (pintype "passive+no_connect"))
    )
    (net (code "93") (name "unconnected-(K5-Pad3)") (class "Default")
      (node (ref "K5") (pin "3") (pinfunction "3_3") (pintype "passive+no_connect"))
    )
    (net (code "94") (name "unconnected-(K6-Pad3)") (class "Default")
      (node (ref "K6") (pin "3") (pinfunction "3_3") (pintype "passive+no_connect"))
    )
    (net (code "95") (name "unconnected-(K7-Pad3)") (class "Default")
      (node (ref "K7") (pin "3") (pinfunction "3_3") (pintype "passive+no_connect"))
    )
    (net (code "96") (name "unconnected-(K8-Pad3)") (class "Default")
      (node (ref "K8") (pin "3") (pinfunction "3_3") (pintype "passive+no_connect"))
    )
    (net (code "97") (name "unconnected-(K9-Pad3)") (class "Default")
      (node (ref "K9") (pin "3") (pinfunction "3_3") (pintype "passive+no_connect"))
    )
    (net (code "98") (name "unconnected-(K10-Pad3)") (class "Default")
      (node (ref "K10") (pin "3") (pinfunction "3_3") (pintype "passive+no_connect"))
    )
    (net (code "99") (name "unconnected-(K11-Pad3)") (class "Default")
      (node (ref "K11") (pin "3") (pinfunction "3_3") (pintype "passive+no_connect"))
    )
    (net (code "100") (name "unconnected-(K12-Pad3)") (class "Default")
      (node (ref "K12") (pin "3") (pinfunction "3_3") (pintype "passive+no_connect"))
    )
    (net (code "101") (name "unconnected-(K13-Pad3)") (class "Default")
      (node (ref "K13") (pin "3") (pinfunction "3_3") (pintype "passive+no_connect"))
    )
    (net (code "102") (name "unconnected-(K14-Pad3)") (class "Default")
      (node (ref "K14") (pin "3") (pinfunction "3_3") (pintype "passive+no_connect"))
    )
    (net (code "103") (name "unconnected-(K15-Pad3)") (class "Default")
      (node (ref "K15") (pin "3") (pinfunction "3_3") (pintype "passive+no_connect"))
    )
    (net (code "104") (name "unconnected-(K16-Pad3)") (class "Default")
      (node (ref "K16") (pin "3") (pinfunction "3_3") (pintype "passive+no_connect"))
    )
    (net (code "105") (name "unconnected-(U13-3B-Pad3)") (class "Default")
      (node (ref "U13") (pin "3") (pinfunction "3B_3") (pintype "passive+no_connect"))
    )
    (net (code "106") (name "unconnected-(U13-3C-Pad14)") (class "Default")
      (node (ref "U13") (pin "14") (pinfunction "3C_14") (pintype "passive+no_connect"))
    )
    (net (code "107") (name "unconnected-(U13-4B-Pad4)") (class "Default")
      (node (ref "U13") (pin "4") (pinfunction "4B_4") (pintype "passive+no_connect"))
    )
    (net (code "108") (name "unconnected-(U13-4C-Pad13)") (class "Default")
      (node (ref "U13") (pin "13") (pinfunction "4C_13") (pintype "passive+no_connect"))
    )
    (net (code "109") (name "unconnected-(U13-5B-Pad5)") (class "Default")
      (node (ref "U13") (pin "5") (pinfunction "5B_5") (pintype "passive+no_connect"))
    )
    (net (code "110") (name "unconnected-(U13-5C-Pad12)") (class "Default")
      (node (ref "U13") (pin "12") (pinfunction "5C_12") (pintype "passive+no_connect"))
    )
    (net (code "111") (name "unconnected-(U13-6B-Pad6)") (class "Default")
      (node (ref "U13") (pin "6") (pinfunction "6B_6") (pintype "passive+no_connect"))
    )
    (net (code "112") (name "unconnected-(U13-6C-Pad11)") (class "Default")
      (node (ref "U13") (pin "11") (pinfunction "6C_11") (pintype "passive+no_connect"))
    )
    (net (code "113") (name "unconnected-(U13-7B-Pad7)") (class "Default")
      (node (ref "U13") (pin "7") (pinfunction "7B_7") (pintype "passive+no_connect"))
    )
    (net (code "114") (name "unconnected-(U13-7C-Pad10)") (class "Default")
      (node (ref "U13") (pin "10") (pinfunction "7C_10") (pintype "passive+no_connect"))
    )
  )
)
